# Sheet2.net
KiCad netlist of a schematic drawn in Altium Designer
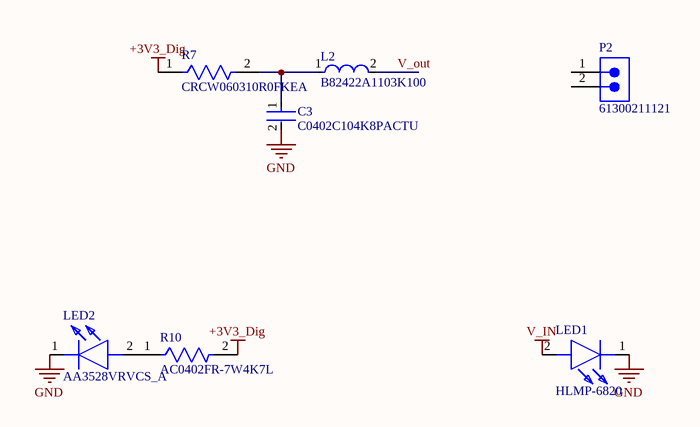
[diagram p0: Sheet2.SchDoc]

(export (version "E")
  (design (tool "Eeschema 10.0.6"))
  (components
    (comp (ref "C3")
      (value "C0402C104K8PACTU")
      (footprint "FP-C0402-BB-MFG")
      (description "CAP CER 0.1UF 10V X5R 0402")
      (fields (field (name "MANUFACTURER") "Kemet") (field (name "TOLERANCE") "0.1"))
      (libsource (lib "Altium Content Vault") (part "b4654b650e69147ec39a6b967a45e02"))
    )
    (comp (ref "L2")
      (value "B82422A1103K100")
      (footprint "FP-B82422A-MFG")
      (description "FIXED IND 10UH 180MA 1.6 OHM SMD")
      (fields (field (name "TOLERANCE") "10%"))
      (libsource (lib "Altium Content Vault") (part "725321dda6339637d4d059423bc1c3c"))
    )
    (comp (ref "LED1")
      (value "HLMP-6820")
      (footprint "SamacSys:HLMP6820")
      (description "LED")
      (fields (field (name "MOUSER PART NUMBER") "630-HLMP-6820"))
      (libsource (lib "*") (part "HLMP-6820"))
    )
    (comp (ref "LED2")
      (value "AA3528VRVCS_A")
      (footprint "SamacSys:LEDM3528X210N")
      (description "LED")
      (fields
        (field (name "MANUFACTURER_PART_NUMBER") "AA3528VRVCS/A")
        (field (name "MOUSER PART NUMBER") "604-AA3528VRVCS/A")
      )
      (libsource (lib "*") (part "AA3528VRVCS_A"))
    )
    (comp (ref "P2")
      (value "61300211121")
      (footprint "61300211121")
      (libsource (lib "Altium Content Vault") (part "Header_Male_1R_02P"))
    )
    (comp (ref "R7")
      (value "CRCW060310R0FKEA")
      (footprint "FP-CRCW0603-e3-IPC_A")
      (description "RES Thick Film, 10Ω, 1%, 0.1W, 100ppm/°C, 0603")
      (fields (field (name "TOLERANCE") "1%"))
      (libsource (lib "Altium Content Vault") (part "1029c3af85768c4190bb7ad29bc67b5"))
    )
    (comp (ref "R10")
      (value "AC0402FR-7W4K7L")
      (footprint "FP-AC0402-MFG")
      (description "RES 4.7kΩ ±1% 0.125W 0402")
      (libsource (lib "Altium Content Vault") (part "1029c3af85768c4190bb7ad29bc67b5"))
    )
  )
  (nets
    (net (code "1") (name "+3V3_Dig") (class "Default")
      (node (ref "R10") (pin "2") (pinfunction "2_2") (pintype "passive"))
      (node (ref "R7") (pin "1") (pinfunction "1_1") (pintype "passive"))
    )
    (net (code "2") (name "/V_out") (class "Default")
      (node (ref "L2") (pin "2") (pinfunction "2_2") (pintype "passive"))
    )
    (net (code "3") (name "GND") (class "Default")
      (node (ref "C3") (pin "2") (pinfunction "2_2") (pintype "passive"))
      (node (ref "LED1") (pin "1") (pinfunction "K_1") (pintype "passive"))
      (node (ref "LED2") (pin "1") (pinfunction "K_1") (pintype "passive"))
    )
    (net (code "4") (name "Net-(C3-Pad1)") (class "Default")
      (node (ref "C3") (pin "1") (pinfunction "1_1") (pintype "passive"))
      (node (ref "L2") (pin "1") (pinfunction "1_1") (pintype "passive"))
      (node (ref "R7") (pin "2") (pinfunction "2_2") (pintype "passive"))
    )
    (net (code "5") (name "Net-(LED2-A)") (class "Default")
      (node (ref "LED2") (pin "2") (pinfunction "A_2") (pintype "passive"))
      (node (ref "R10") (pin "1") (pinfunction "1_1") (pintype "passive"))
    )
    (net (code "6") (name "V_IN") (class "Default")
      (node (ref "LED1") (pin "2") (pinfunction "A_2") (pintype "passive"))
    )
    (net (code "7") (name "unconnected-(P2-Pad1)") (class "Default")
      (node (ref "P2") (pin "1") (pinfunction "1_1") (pintype "passive"))
    )
    (net (code "8") (name "unconnected-(P2-Pad2)") (class "Default")
      (node (ref "P2") (pin "2") (pinfunction "2_2") (pintype "passive"))
    )
  )
)
